# CPU-board-Sheet3-multi-rev_0_1.net
KiCad netlist of a schematic drawn in Altium Designer
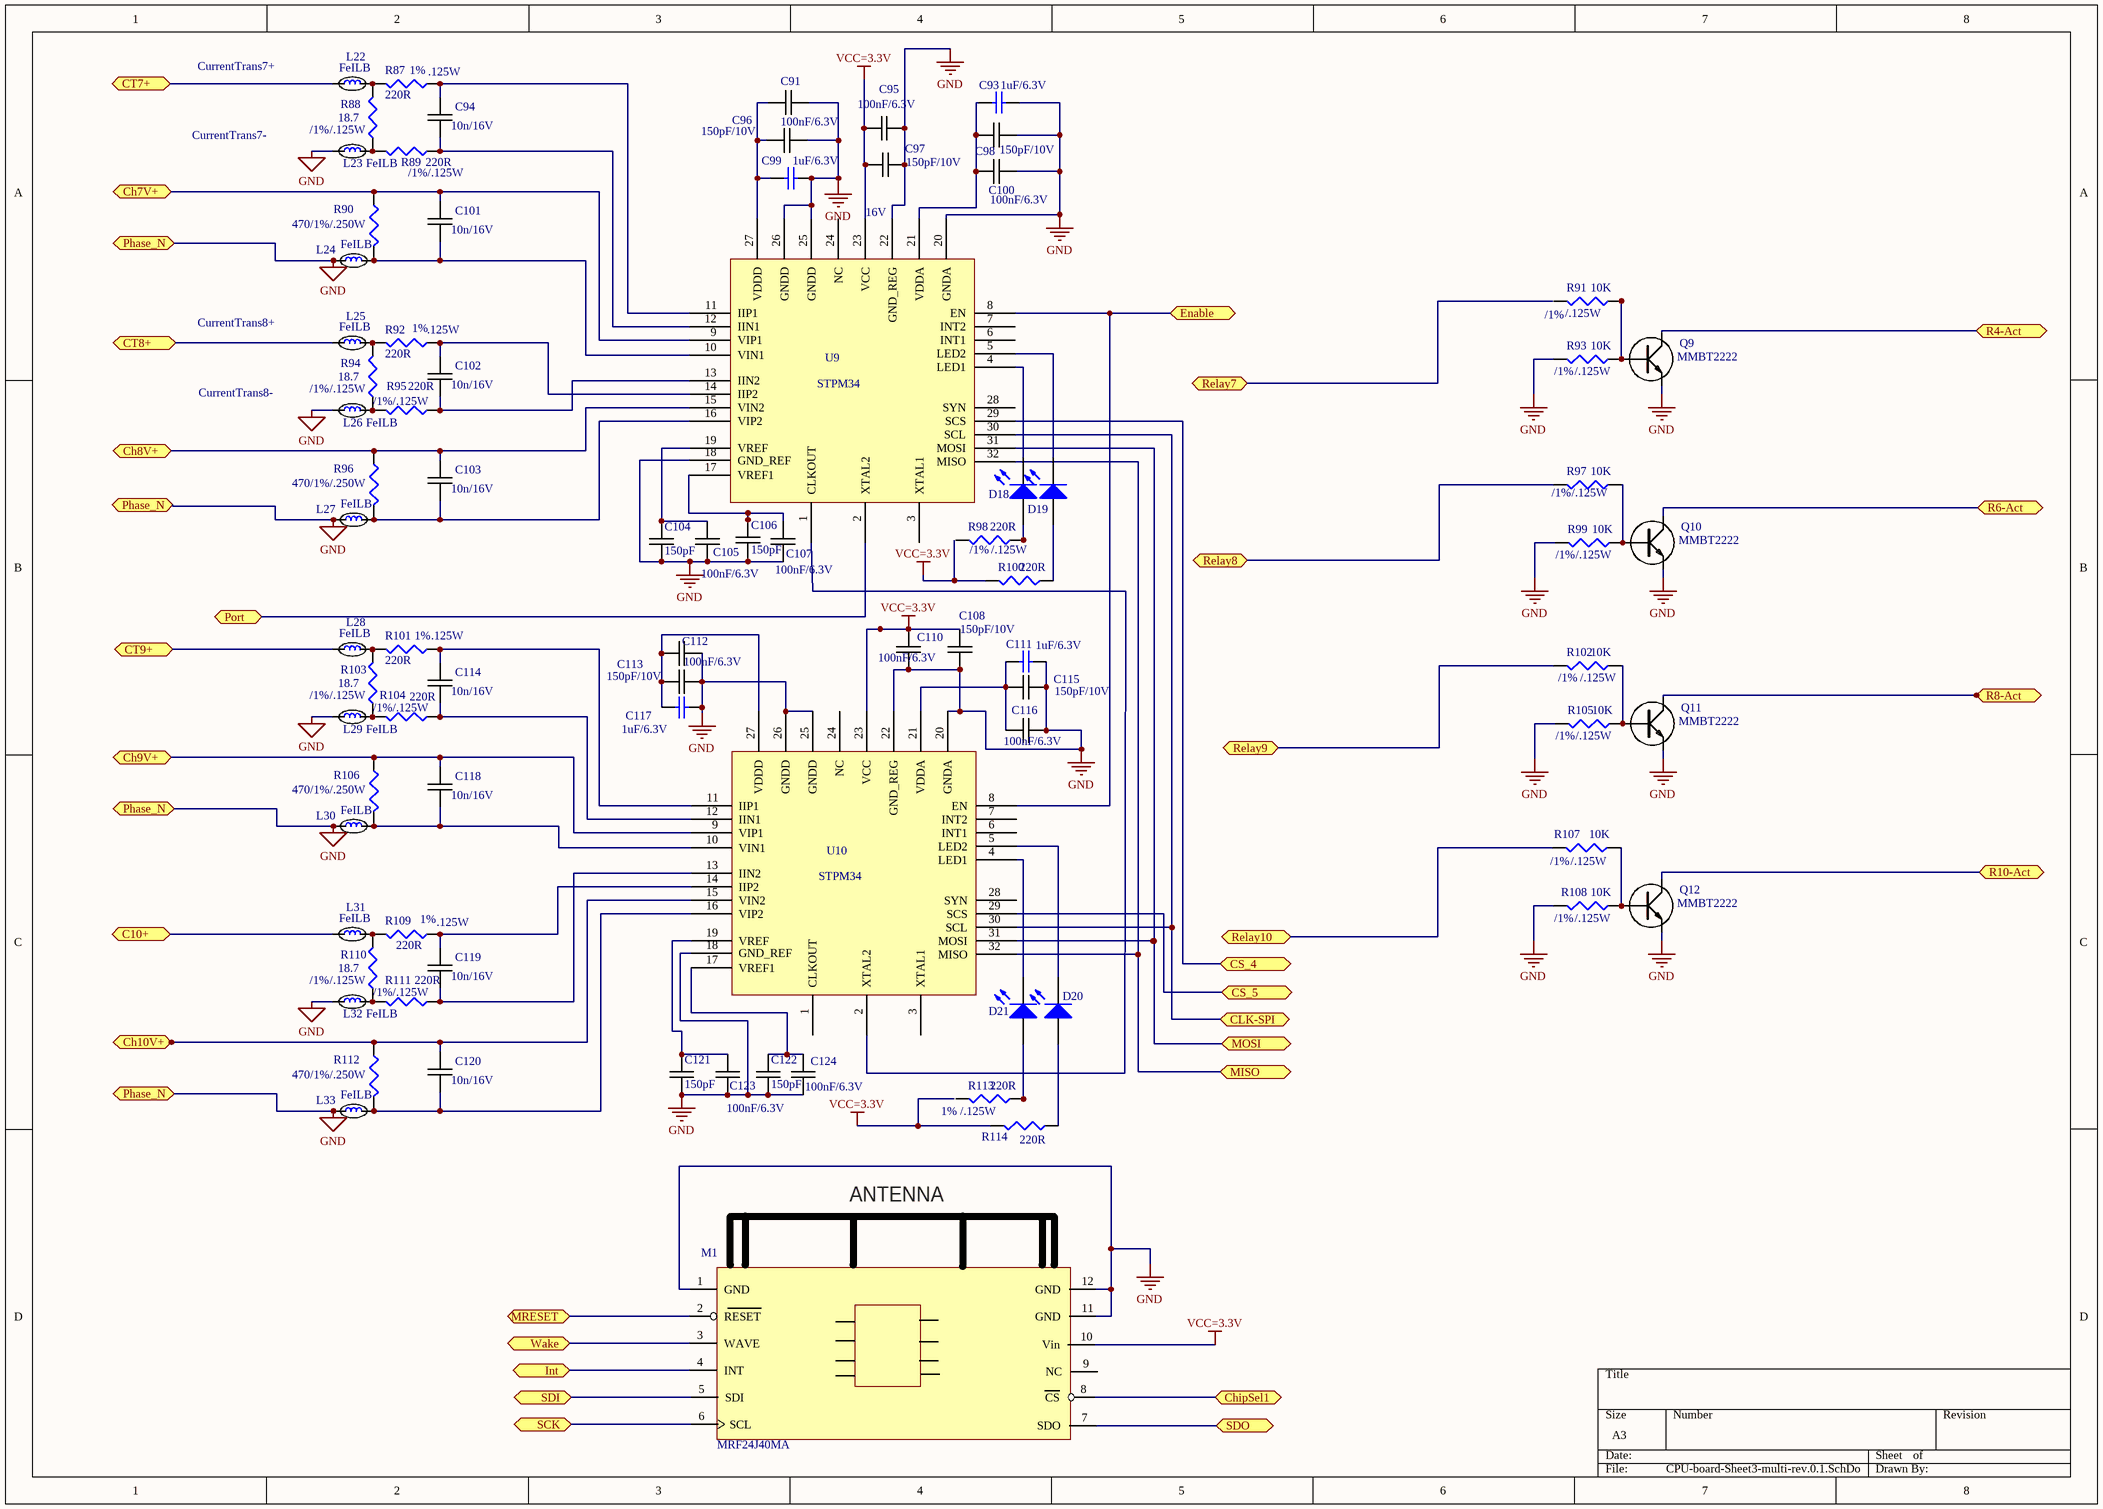
[diagram p0: CPU-board-Sheet3-multi-rev.0.1.SchDoc]

(export (version "E")
  (design (tool "Eeschema 10.0.6"))
  (components
    (comp (ref "C91")
      (value "100nF/6.3V")
      (footprint "0402C-GENERIC")
      (description "CAPACITOR 0805 CERAMIC")
      (fields (field (name "MANUFACTURER") "Taiyo Yuden"))
      (libsource (lib "vh_altium_library") (part "0805C-18PF-50V-C0G-JOH"))
    )
    (comp (ref "C93")
      (value "1uF/6.3V")
      (footprint "0402C-GENERIC")
      (description "Capacitor")
      (fields (field (name "MANUFACTURER") "Murata") (field (name "PUBLISHER") "Altium Limited"))
      (libsource (lib "Miscellaneous Devices") (part "Cap"))
    )
    (comp (ref "C94")
      (value "10n/16V")
      (footprint "0402C-GENERIC")
      (description "CAPACITOR 0805 CERAMIC")
      (fields (field (name "MANUFACTURER") "Murata Electronics"))
      (libsource (lib "vh_altium_library") (part "0805C-18PF-50V-C0G-JOH"))
    )
    (comp (ref "C95")
      (value "100nF/6.3V")
      (footprint "0402C-GENERIC")
      (description "CAPACITOR 0805 CERAMIC")
      (fields (field (name "MANUFACTURER") "Taiyo Yuden"))
      (libsource (lib "vh_altium_library") (part "0805C-18PF-50V-C0G-JOH"))
    )
    (comp (ref "C96")
      (value "150pF/10V")
      (footprint "0402C-GENERIC")
      (description "CAPACITOR 0805 CERAMIC")
      (fields (field (name "MANUFACTURER") "Wurth Electronics"))
      (libsource (lib "vh_altium_library") (part "0805C-18PF-50V-C0G-JOH"))
    )
    (comp (ref "C97")
      (value "150pF/10V")
      (footprint "0402C-GENERIC")
      (description "CAPACITOR 0805 CERAMIC")
      (fields (field (name "MANUFACTURER") "Wurth Electronics"))
      (libsource (lib "vh_altium_library") (part "0805C-18PF-50V-C0G-JOH"))
    )
    (comp (ref "C98")
      (value "150pF/10V")
      (footprint "0402C-GENERIC")
      (description "CAPACITOR 0805 CERAMIC")
      (fields (field (name "MANUFACTURER") "Wurth Electronics"))
      (libsource (lib "vh_altium_library") (part "0805C-18PF-50V-C0G-JOH"))
    )
    (comp (ref "C99")
      (value "1uF/6.3V")
      (footprint "0402C-GENERIC")
      (description "Capacitor")
      (fields (field (name "MANUFACTURER") "Murata") (field (name "PUBLISHER") "Altium Limited"))
      (libsource (lib "Miscellaneous Devices") (part "Cap"))
    )
    (comp (ref "C100")
      (value "100nF/6.3V")
      (footprint "0402C-GENERIC")
      (description "CAPACITOR 0805 CERAMIC")
      (fields (field (name "MANUFACTURER") "Taiyo Yuden"))
      (libsource (lib "vh_altium_library") (part "0805C-18PF-50V-C0G-JOH"))
    )
    (comp (ref "C101")
      (value "10n/16V")
      (footprint "0402C-GENERIC")
      (description "CAPACITOR 0805 CERAMIC")
      (fields (field (name "MANUFACTURER") "Murata Electronics"))
      (libsource (lib "vh_altium_library") (part "0805C-18PF-50V-C0G-JOH"))
    )
    (comp (ref "C102")
      (value "10n/16V")
      (footprint "0402C-GENERIC")
      (description "CAPACITOR 0805 CERAMIC")
      (fields (field (name "MANUFACTURER") "Murata Electronics"))
      (libsource (lib "vh_altium_library") (part "0805C-18PF-50V-C0G-JOH"))
    )
    (comp (ref "C103")
      (value "10n/16V")
      (footprint "0402C-GENERIC")
      (description "CAPACITOR 0805 CERAMIC")
      (fields (field (name "MANUFACTURER") "Murata Electronics"))
      (libsource (lib "vh_altium_library") (part "0805C-18PF-50V-C0G-JOH"))
    )
    (comp (ref "C104")
      (value "150pF")
      (footprint "0402C-GENERIC")
      (description "CAPACITOR 0805 CERAMIC")
      (fields (field (name "MANUFACTURER") "Wurth Electronics"))
      (libsource (lib "vh_altium_library") (part "0805C-18PF-50V-C0G-JOH"))
    )
    (comp (ref "C105")
      (value "100nF/6.3V")
      (footprint "0402C-GENERIC")
      (description "CAPACITOR 0805 CERAMIC")
      (fields (field (name "MANUFACTURER") "Taiyo Yuden"))
      (libsource (lib "vh_altium_library") (part "0805C-18PF-50V-C0G-JOH"))
    )
    (comp (ref "C106")
      (value "150pF")
      (footprint "0402C-GENERIC")
      (description "CAPACITOR 0805 CERAMIC")
      (fields (field (name "MANUFACTURER") "Wurth Electronics"))
      (libsource (lib "vh_altium_library") (part "0805C-18PF-50V-C0G-JOH"))
    )
    (comp (ref "C107")
      (value "100nF/6.3V")
      (footprint "0402C-GENERIC")
      (description "CAPACITOR 0805 CERAMIC")
      (fields (field (name "MANUFACTURER") "Taiyo Yuden"))
      (libsource (lib "vh_altium_library") (part "0805C-18PF-50V-C0G-JOH"))
    )
    (comp (ref "C108")
      (value "150pF/10V")
      (footprint "0402C-GENERIC")
      (description "CAPACITOR 0805 CERAMIC")
      (fields (field (name "MANUFACTURER") "Wurth Electronics"))
      (libsource (lib "vh_altium_library") (part "0805C-18PF-50V-C0G-JOH"))
    )
    (comp (ref "C110")
      (value "100nF/6.3V")
      (footprint "0402C-GENERIC")
      (description "CAPACITOR 0805 CERAMIC")
      (fields (field (name "MANUFACTURER") "Taiyo Yuden"))
      (libsource (lib "vh_altium_library") (part "0805C-18PF-50V-C0G-JOH"))
    )
    (comp (ref "C111")
      (value "1uF/6.3V")
      (footprint "0402C-GENERIC")
      (description "Capacitor")
      (fields (field (name "MANUFACTURER") "Murata") (field (name "PUBLISHER") "Altium Limited"))
      (libsource (lib "Miscellaneous Devices") (part "Cap"))
    )
    (comp (ref "C112")
      (value "100nF/6.3V")
      (footprint "0402C-GENERIC")
      (description "CAPACITOR 0805 CERAMIC")
      (fields (field (name "MANUFACTURER") "Taiyo Yuden"))
      (libsource (lib "vh_altium_library") (part "0805C-18PF-50V-C0G-JOH"))
    )
    (comp (ref "C113")
      (value "150pF/10V")
      (footprint "0402C-GENERIC")
      (description "CAPACITOR 0805 CERAMIC")
      (fields (field (name "MANUFACTURER") "Wurth Electronics"))
      (libsource (lib "vh_altium_library") (part "0805C-18PF-50V-C0G-JOH"))
    )
    (comp (ref "C114")
      (value "10n/16V")
      (footprint "0402C-GENERIC")
      (description "CAPACITOR 0805 CERAMIC")
      (fields (field (name "MANUFACTURER") "Murata Electronics"))
      (libsource (lib "vh_altium_library") (part "0805C-18PF-50V-C0G-JOH"))
    )
    (comp (ref "C115")
      (value "150pF/10V")
      (footprint "0402C-GENERIC")
      (description "CAPACITOR 0805 CERAMIC")
      (fields (field (name "MANUFACTURER") "Wurth Electronics"))
      (libsource (lib "vh_altium_library") (part "0805C-18PF-50V-C0G-JOH"))
    )
    (comp (ref "C116")
      (value "100nF/6.3V")
      (footprint "0402C-GENERIC")
      (description "CAPACITOR 0805 CERAMIC")
      (fields (field (name "MANUFACTURER") "Taiyo Yuden"))
      (libsource (lib "vh_altium_library") (part "0805C-18PF-50V-C0G-JOH"))
    )
    (comp (ref "C117")
      (value "1uF/6.3V")
      (footprint "0402C-GENERIC")
      (description "Capacitor")
      (fields (field (name "MANUFACTURER") "Murata") (field (name "PUBLISHER") "Altium Limited"))
      (libsource (lib "Miscellaneous Devices") (part "Cap"))
    )
    (comp (ref "C118")
      (value "10n/16V")
      (footprint "0402C-GENERIC")
      (description "CAPACITOR 0805 CERAMIC")
      (fields (field (name "MANUFACTURER") "Murata Electronics"))
      (libsource (lib "vh_altium_library") (part "0805C-18PF-50V-C0G-JOH"))
    )
    (comp (ref "C119")
      (value "10n/16V")
      (footprint "0402C-GENERIC")
      (description "CAPACITOR 0805 CERAMIC")
      (fields (field (name "MANUFACTURER") "Murata Electronics"))
      (libsource (lib "vh_altium_library") (part "0805C-18PF-50V-C0G-JOH"))
    )
    (comp (ref "C120")
      (value "10n/16V")
      (footprint "0402C-GENERIC")
      (description "CAPACITOR 0805 CERAMIC")
      (fields (field (name "MANUFACTURER") "Murata Electronics"))
      (libsource (lib "vh_altium_library") (part "0805C-18PF-50V-C0G-JOH"))
    )
    (comp (ref "C121")
      (value "150pF")
      (footprint "0402C-GENERIC")
      (description "CAPACITOR 0805 CERAMIC")
      (fields (field (name "MANUFACTURER") "Wurth Electronics"))
      (libsource (lib "vh_altium_library") (part "0805C-18PF-50V-C0G-JOH"))
    )
    (comp (ref "C122")
      (value "150pF")
      (footprint "0402C-GENERIC")
      (description "CAPACITOR 0805 CERAMIC")
      (fields (field (name "MANUFACTURER") "Wurth Electronics"))
      (libsource (lib "vh_altium_library") (part "0805C-18PF-50V-C0G-JOH"))
    )
    (comp (ref "C123")
      (value "100nF/6.3V")
      (footprint "0402C-GENERIC")
      (description "CAPACITOR 0805 CERAMIC")
      (fields (field (name "MANUFACTURER") "Taiyo Yuden"))
      (libsource (lib "vh_altium_library") (part "0805C-18PF-50V-C0G-JOH"))
    )
    (comp (ref "C124")
      (value "100nF/6.3V")
      (footprint "0402C-GENERIC")
      (description "CAPACITOR 0805 CERAMIC")
      (fields (field (name "MANUFACTURER") "Taiyo Yuden"))
      (libsource (lib "vh_altium_library") (part "0805C-18PF-50V-C0G-JOH"))
    )
    (comp (ref "D18")
      (value "LED2")
      (footprint "LED-SM")
      (description "Typical RED, GREEN, YELLOW, AMBER GaAs LED")
      (fields (field (name "MANUFACTURER") "Lite-On Inc") (field (name "PUBLISHER") "Altium Limited"))
      (libsource (lib "Miscellaneous Devices") (part "LED2"))
    )
    (comp (ref "D19")
      (value "LED2")
      (footprint "LED-SM")
      (description "Typical RED, GREEN, YELLOW, AMBER GaAs LED")
      (fields (field (name "MANUFACTURER") "Lite-On Inc") (field (name "PUBLISHER") "Altium Limited"))
      (libsource (lib "Miscellaneous Devices") (part "LED2"))
    )
    (comp (ref "D20")
      (value "LED2")
      (footprint "LED-SM")
      (description "Typical RED, GREEN, YELLOW, AMBER GaAs LED")
      (fields (field (name "MANUFACTURER") "Lite-On Inc") (field (name "PUBLISHER") "Altium Limited"))
      (libsource (lib "Miscellaneous Devices") (part "LED2"))
    )
    (comp (ref "D21")
      (value "LED2")
      (footprint "LED-SM")
      (description "Typical RED, GREEN, YELLOW, AMBER GaAs LED")
      (fields (field (name "MANUFACTURER") "Lite-On Inc") (field (name "PUBLISHER") "Altium Limited"))
      (libsource (lib "Miscellaneous Devices") (part "LED2"))
    )
    (comp (ref "L22")
      (value "FeILB")
      (footprint "0603C-TBD")
      (fields (field (name "MANUFACTURER") "Brand Samsung"))
      (libsource (lib "SMLib") (part "FerrBeads/ILBB"))
    )
    (comp (ref "L23")
      (value "FeILB")
      (footprint "0603C-TBD")
      (fields (field (name "MANUFACTURER") "Brand Samsung"))
      (libsource (lib "SMLib") (part "FerrBeads/ILBB"))
    )
    (comp (ref "L24")
      (value "FeILB")
      (footprint "0603C-TBD")
      (fields (field (name "MANUFACTURER") "Brand Samsung"))
      (libsource (lib "SMLib") (part "FerrBeads/ILBB"))
    )
    (comp (ref "L25")
      (value "FeILB")
      (footprint "0603C-TBD")
      (fields (field (name "MANUFACTURER") "Brand Samsung"))
      (libsource (lib "SMLib") (part "FerrBeads/ILBB"))
    )
    (comp (ref "L26")
      (value "FeILB")
      (footprint "0603C-TBD")
      (fields (field (name "MANUFACTURER") "Brand Samsung"))
      (libsource (lib "SMLib") (part "FerrBeads/ILBB"))
    )
    (comp (ref "L27")
      (value "FeILB")
      (footprint "0603C-TBD")
      (fields (field (name "MANUFACTURER") "Brand Samsung"))
      (libsource (lib "SMLib") (part "FerrBeads/ILBB"))
    )
    (comp (ref "L28")
      (value "FeILB")
      (footprint "0603C-TBD")
      (fields (field (name "MANUFACTURER") "Brand Samsung"))
      (libsource (lib "SMLib") (part "FerrBeads/ILBB"))
    )
    (comp (ref "L29")
      (value "FeILB")
      (footprint "0603C-TBD")
      (fields (field (name "MANUFACTURER") "Brand Samsung"))
      (libsource (lib "SMLib") (part "FerrBeads/ILBB"))
    )
    (comp (ref "L30")
      (value "FeILB")
      (footprint "0603C-TBD")
      (fields (field (name "MANUFACTURER") "Brand Samsung"))
      (libsource (lib "SMLib") (part "FerrBeads/ILBB"))
    )
    (comp (ref "L31")
      (value "FeILB")
      (footprint "0603C-TBD")
      (fields (field (name "MANUFACTURER") "Brand Samsung"))
      (libsource (lib "SMLib") (part "FerrBeads/ILBB"))
    )
    (comp (ref "L32")
      (value "FeILB")
      (footprint "0603C-TBD")
      (fields (field (name "MANUFACTURER") "Brand Samsung"))
      (libsource (lib "SMLib") (part "FerrBeads/ILBB"))
    )
    (comp (ref "L33")
      (value "FeILB")
      (footprint "0603C-TBD")
      (fields (field (name "MANUFACTURER") "Brand Samsung"))
      (libsource (lib "SMLib") (part "FerrBeads/ILBB"))
    )
    (comp (ref "M1")
      (value "MRF24J40MA")
      (footprint "MRF24J40MA-zigBEE module")
      (fields (field (name "MANUFACTURER") "Microchip"))
      (libsource (lib "SMLib") (part "MRF24J40MA"))
    )
    (comp (ref "Q9")
      (value "MMBT2222")
      (footprint "MMBT2222")
      (description "BC847 SMALL SIGNAL NPN TRANSISTOR")
      (fields (field (name "MANUFACTURER") "Diodes  Inc."))
      (libsource (lib "vh_altium_library") (part "MMBT2222"))
    )
    (comp (ref "Q10")
      (value "MMBT2222")
      (footprint "MMBT2222")
      (description "BC847 SMALL SIGNAL NPN TRANSISTOR")
      (fields (field (name "MANUFACTURER") "Diodes  Inc."))
      (libsource (lib "vh_altium_library") (part "MMBT2222"))
    )
    (comp (ref "Q11")
      (value "MMBT2222")
      (footprint "MMBT2222")
      (description "BC847 SMALL SIGNAL NPN TRANSISTOR")
      (fields (field (name "MANUFACTURER") "Diodes  Inc."))
      (libsource (lib "vh_altium_library") (part "MMBT2222"))
    )
    (comp (ref "Q12")
      (value "MMBT2222")
      (footprint "MMBT2222")
      (description "BC847 SMALL SIGNAL NPN TRANSISTOR")
      (fields (field (name "MANUFACTURER") "Diodes  Inc."))
      (libsource (lib "vh_altium_library") (part "MMBT2222"))
    )
    (comp (ref "R87")
      (value "220R")
      (footprint "0402R-TBD")
      (description "Resistor")
      (fields (field (name "MANUFACTURER") "Panasonic") (field (name "PUBLISHER") "Altium Limited"))
      (libsource (lib "Miscellaneous Devices") (part "Res3"))
    )
    (comp (ref "R88")
      (value "18.7")
      (footprint "0402R-TBD")
      (description "Resistor")
      (fields (field (name "MANUFACTURER") "Panasonic") (field (name "PUBLISHER") "Altium Limited"))
      (libsource (lib "Miscellaneous Devices") (part "Res3"))
    )
    (comp (ref "R89")
      (value "220R")
      (footprint "0402R-TBD")
      (description "Resistor")
      (fields (field (name "MANUFACTURER") "Panasonic") (field (name "PUBLISHER") "Altium Limited"))
      (libsource (lib "Miscellaneous Devices") (part "Res3"))
    )
    (comp (ref "R90")
      (value "470/1%/.250W")
      (footprint "1206FB-GENERIC")
      (description "Resistor")
      (fields (field (name "MANUFACTURER") "Panasonic Co") (field (name "PUBLISHER") "Altium Limited"))
      (libsource (lib "Miscellaneous Devices") (part "Res3"))
    )
    (comp (ref "R91")
      (value "10K")
      (footprint "0402R-TBD")
      (description "Resistor")
      (fields (field (name "MANUFACTURER") "Panasonic") (field (name "PUBLISHER") "Altium Limited"))
      (libsource (lib "Miscellaneous Devices") (part "Res3"))
    )
    (comp (ref "R92")
      (value "220R")
      (footprint "0402R-TBD")
      (description "Resistor")
      (fields (field (name "MANUFACTURER") "Panasonic") (field (name "PUBLISHER") "Altium Limited"))
      (libsource (lib "Miscellaneous Devices") (part "Res3"))
    )
    (comp (ref "R93")
      (value "10K")
      (footprint "0402R-TBD")
      (description "Resistor")
      (fields (field (name "MANUFACTURER") "Panasonic") (field (name "PUBLISHER") "Altium Limited"))
      (libsource (lib "Miscellaneous Devices") (part "Res3"))
    )
    (comp (ref "R94")
      (value "18.7")
      (footprint "0402R-TBD")
      (description "Resistor")
      (fields (field (name "MANUFACTURER") "Panasonic") (field (name "PUBLISHER") "Altium Limited"))
      (libsource (lib "Miscellaneous Devices") (part "Res3"))
    )
    (comp (ref "R95")
      (value "220R")
      (footprint "0402R-TBD")
      (description "Resistor")
      (fields (field (name "MANUFACTURER") "Panasonic") (field (name "PUBLISHER") "Altium Limited"))
      (libsource (lib "Miscellaneous Devices") (part "Res3"))
    )
    (comp (ref "R96")
      (value "470/1%/.250W")
      (footprint "1206FB-GENERIC")
      (description "Resistor")
      (fields (field (name "MANUFACTURER") "Panasonic Co") (field (name "PUBLISHER") "Altium Limited"))
      (libsource (lib "Miscellaneous Devices") (part "Res3"))
    )
    (comp (ref "R97")
      (value "10K")
      (footprint "0402R-TBD")
      (description "Resistor")
      (fields (field (name "MANUFACTURER") "Panasonic") (field (name "PUBLISHER") "Altium Limited"))
      (libsource (lib "Miscellaneous Devices") (part "Res3"))
    )
    (comp (ref "R98")
      (value "220R")
      (footprint "0402R-TBD")
      (description "Resistor")
      (fields (field (name "MANUFACTURER") "Panasonic") (field (name "PUBLISHER") "Altium Limited"))
      (libsource (lib "Miscellaneous Devices") (part "Res3"))
    )
    (comp (ref "R99")
      (value "10K")
      (footprint "0402R-TBD")
      (description "Resistor")
      (fields (field (name "MANUFACTURER") "Panasonic") (field (name "PUBLISHER") "Altium Limited"))
      (libsource (lib "Miscellaneous Devices") (part "Res3"))
    )
    (comp (ref "R100")
      (value "220R")
      (footprint "0402R-TBD")
      (description "Resistor")
      (fields (field (name "MANUFACTURER") "Panasonic") (field (name "PUBLISHER") "Altium Limited"))
      (libsource (lib "Miscellaneous Devices") (part "Res3"))
    )
    (comp (ref "R101")
      (value "220R")
      (footprint "0402R-TBD")
      (description "Resistor")
      (fields (field (name "MANUFACTURER") "Panasonic") (field (name "PUBLISHER") "Altium Limited"))
      (libsource (lib "Miscellaneous Devices") (part "Res3"))
    )
    (comp (ref "R102")
      (value "10K")
      (footprint "0402R-TBD")
      (description "Resistor")
      (fields (field (name "MANUFACTURER") "Panasonic") (field (name "PUBLISHER") "Altium Limited"))
      (libsource (lib "Miscellaneous Devices") (part "Res3"))
    )
    (comp (ref "R103")
      (value "18.7")
      (footprint "0402R-TBD")
      (description "Resistor")
      (fields (field (name "MANUFACTURER") "Panasonic") (field (name "PUBLISHER") "Altium Limited"))
      (libsource (lib "Miscellaneous Devices") (part "Res3"))
    )
    (comp (ref "R104")
      (value "220R")
      (footprint "0402R-TBD")
      (description "Resistor")
      (fields (field (name "MANUFACTURER") "Panasonic") (field (name "PUBLISHER") "Altium Limited"))
      (libsource (lib "Miscellaneous Devices") (part "Res3"))
    )
    (comp (ref "R105")
      (value "10K")
      (footprint "0402R-TBD")
      (description "Resistor")
      (fields (field (name "MANUFACTURER") "Panasonic") (field (name "PUBLISHER") "Altium Limited"))
      (libsource (lib "Miscellaneous Devices") (part "Res3"))
    )
    (comp (ref "R106")
      (value "470/1%/.250W")
      (footprint "1206FB-GENERIC")
      (description "Resistor")
      (fields (field (name "MANUFACTURER") "Panasonic Co") (field (name "PUBLISHER") "Altium Limited"))
      (libsource (lib "Miscellaneous Devices") (part "Res3"))
    )
    (comp (ref "R107")
      (value "10K")
      (footprint "0402R-TBD")
      (description "Resistor")
      (fields (field (name "MANUFACTURER") "Panasonic") (field (name "PUBLISHER") "Altium Limited"))
      (libsource (lib "Miscellaneous Devices") (part "Res3"))
    )
    (comp (ref "R108")
      (value "10K")
      (footprint "0402R-TBD")
      (description "Resistor")
      (fields (field (name "MANUFACTURER") "Panasonic") (field (name "PUBLISHER") "Altium Limited"))
      (libsource (lib "Miscellaneous Devices") (part "Res3"))
    )
    (comp (ref "R109")
      (value "220R")
      (footprint "0402R-TBD")
      (description "Resistor")
      (fields (field (name "MANUFACTURER") "Panasonic") (field (name "PUBLISHER") "Altium Limited"))
      (libsource (lib "Miscellaneous Devices") (part "Res3"))
    )
    (comp (ref "R110")
      (value "18.7")
      (footprint "0402R-TBD")
      (description "Resistor")
      (fields (field (name "MANUFACTURER") "Panasonic") (field (name "PUBLISHER") "Altium Limited"))
      (libsource (lib "Miscellaneous Devices") (part "Res3"))
    )
    (comp (ref "R111")
      (value "220R")
      (footprint "0402R-TBD")
      (description "Resistor")
      (fields (field (name "MANUFACTURER") "Panasonic") (field (name "PUBLISHER") "Altium Limited"))
      (libsource (lib "Miscellaneous Devices") (part "Res3"))
    )
    (comp (ref "R112")
      (value "470/1%/.250W")
      (footprint "1206FB-GENERIC")
      (description "Resistor")
      (fields (field (name "MANUFACTURER") "Panasonic Co") (field (name "PUBLISHER") "Altium Limited"))
      (libsource (lib "Miscellaneous Devices") (part "Res3"))
    )
    (comp (ref "R113")
      (value "220R")
      (footprint "0402R-TBD")
      (description "Resistor")
      (fields (field (name "MANUFACTURER") "Panasonic") (field (name "PUBLISHER") "Altium Limited"))
      (libsource (lib "Miscellaneous Devices") (part "Res3"))
    )
    (comp (ref "R114")
      (value "220R")
      (footprint "0402R-TBD")
      (description "Resistor")
      (fields (field (name "MANUFACTURER") "Panasonic") (field (name "PUBLISHER") "Altium Limited"))
      (libsource (lib "Miscellaneous Devices") (part "Res3"))
    )
    (comp (ref "U9")
      (value "STPM34")
      (footprint "Atmel Microcontroller 8-Bit megaAVR:QFN32_L")
      (libsource (lib "SMLib") (part "STPM34"))
    )
    (comp (ref "U10")
      (value "STPM34")
      (footprint "Atmel Microcontroller 8-Bit megaAVR:QFN32_L")
      (libsource (lib "SMLib") (part "STPM34"))
    )
  )
  (nets
    (net (code "1") (name "/C10+") (class "Default")
      (node (ref "L31") (pin "1") (pinfunction "1_1") (pintype "passive"))
    )
    (net (code "2") (name "/CLK-SPI") (class "Default")
      (node (ref "U10") (pin "30") (pinfunction "SCL_30") (pintype "passive"))
      (node (ref "U9") (pin "30") (pinfunction "SCL_30") (pintype "passive"))
    )
    (net (code "3") (name "/CS_4") (class "Default")
      (node (ref "U9") (pin "29") (pinfunction "SCS_29") (pintype "passive"))
    )
    (net (code "4") (name "/CS_5") (class "Default")
      (node (ref "U10") (pin "29") (pinfunction "SCS_29") (pintype "passive"))
    )
    (net (code "5") (name "/CT7+") (class "Default")
      (node (ref "L22") (pin "1") (pinfunction "1_1") (pintype "passive"))
    )
    (net (code "6") (name "/CT8+") (class "Default")
      (node (ref "L25") (pin "1") (pinfunction "1_1") (pintype "passive"))
    )
    (net (code "7") (name "/CT9+") (class "Default")
      (node (ref "L28") (pin "1") (pinfunction "1_1") (pintype "passive"))
    )
    (net (code "8") (name "/Ch7V+") (class "Default")
      (node (ref "C101") (pin "2") (pintype "passive"))
      (node (ref "R90") (pin "1") (pinfunction "1_1") (pintype "passive"))
      (node (ref "U9") (pin "9") (pinfunction "VIP1_9") (pintype "passive"))
    )
    (net (code "9") (name "/Ch8V+") (class "Default")
      (node (ref "C103") (pin "2") (pintype "passive"))
      (node (ref "R96") (pin "1") (pinfunction "1_1") (pintype "passive"))
      (node (ref "U9") (pin "15") (pinfunction "VIN2_15") (pintype "passive"))
    )
    (net (code "10") (name "/Ch9V+") (class "Default")
      (node (ref "C118") (pin "2") (pintype "passive"))
      (node (ref "R106") (pin "1") (pinfunction "1_1") (pintype "passive"))
      (node (ref "U10") (pin "9") (pinfunction "VIP1_9") (pintype "passive"))
    )
    (net (code "11") (name "/Ch10V+") (class "Default")
      (node (ref "C120") (pin "2") (pintype "passive"))
      (node (ref "R112") (pin "1") (pinfunction "1_1") (pintype "passive"))
      (node (ref "U10") (pin "15") (pinfunction "VIN2_15") (pintype "passive"))
    )
    (net (code "12") (name "/ChipSel1") (class "Default")
      (node (ref "M1") (pin "8") (pinfunction "CS_8") (pintype "passive"))
    )
    (net (code "13") (name "/Enable") (class "Default")
      (node (ref "U10") (pin "8") (pinfunction "EN_8") (pintype "passive"))
      (node (ref "U9") (pin "8") (pinfunction "EN_8") (pintype "passive"))
    )
    (net (code "14") (name "/Int") (class "Default")
      (node (ref "M1") (pin "4") (pinfunction "INT_4") (pintype "passive"))
    )
    (net (code "15") (name "/MISO") (class "Default")
      (node (ref "U10") (pin "32") (pinfunction "MISO_32") (pintype "passive"))
      (node (ref "U9") (pin "32") (pinfunction "MISO_32") (pintype "passive"))
    )
    (net (code "16") (name "/MOSI") (class "Default")
      (node (ref "U10") (pin "31") (pinfunction "MOSI_31") (pintype "passive"))
      (node (ref "U9") (pin "31") (pinfunction "MOSI_31") (pintype "passive"))
    )
    (net (code "17") (name "/MRESET") (class "Default")
      (node (ref "M1") (pin "2") (pinfunction "RESET_2") (pintype "passive"))
    )
    (net (code "18") (name "/Port") (class "Default")
      (node (ref "U9") (pin "2") (pinfunction "XTAL2_2") (pintype "passive"))
    )
    (net (code "19") (name "/R4-Act") (class "Default") (node (ref "Q9") (pin "C") (pintype "passive")))
    (net (code "20") (name "/R6-Act") (class "Default") (node (ref "Q10") (pin "C") (pintype "passive")))
    (net (code "21") (name "/R8-Act") (class "Default") (node (ref "Q11") (pin "C") (pintype "passive")))
    (net (code "22") (name "/R10-Act") (class "Default") (node (ref "Q12") (pin "C") (pintype "passive")))
    (net (code "24") (name "/Relay8") (class "Default")
      (node (ref "R97") (pin "2") (pinfunction "2_2") (pintype "passive"))
    )
    (net (code "25") (name "/Relay9") (class "Default")
      (node (ref "R102") (pin "2") (pinfunction "2_2") (pintype "passive"))
    )
    (net (code "26") (name "/Relay10") (class "Default")
      (node (ref "R107") (pin "2") (pinfunction "2_2") (pintype "passive"))
    )
    (net (code "27") (name "/SCK") (class "Default")
      (node (ref "M1") (pin "6") (pinfunction "SCL_6") (pintype "passive"))
    )
    (net (code "28") (name "/SDI") (class "Default")
      (node (ref "M1") (pin "5") (pinfunction "SDI_5") (pintype "passive"))
    )
    (net (code "29") (name "/SDO") (class "Default")
      (node (ref "M1") (pin "7") (pinfunction "SDO_7") (pintype "passive"))
    )
    (net (code "30") (name "/Wake") (class "Default")
      (node (ref "M1") (pin "3") (pinfunction "WAVE_3") (pintype "passive"))
    )
    (net (code "31") (name "GND") (class "Default")
      (node (ref "C100") (pin "2") (pintype "passive"))
      (node (ref "C104") (pin "2") (pintype "passive"))
      (node (ref "C105") (pin "2") (pintype "passive"))
      (node (ref "C106") (pin "2") (pintype "passive"))
      (node (ref "C107") (pin "2") (pintype "passive"))
      (node (ref "C108") (pin "2") (pintype "passive"))
      (node (ref "C110") (pin "1") (pintype "passive"))
      (node (ref "C111") (pin "2") (pinfunction "2_2") (pintype "passive"))
      (node (ref "C112") (pin "2") (pintype "passive"))
      (node (ref "C113") (pin "2") (pintype "passive"))
      (node (ref "C115") (pin "2") (pintype "passive"))
      (node (ref "C116") (pin "2") (pintype "passive"))
      (node (ref "C117") (pin "2") (pinfunction "2_2") (pintype "passive"))
      (node (ref "C121") (pin "2") (pintype "passive"))
      (node (ref "C122") (pin "2") (pintype "passive"))
      (node (ref "C123") (pin "2") (pintype "passive"))
      (node (ref "C124") (pin "2") (pintype "passive"))
      (node (ref "C91") (pin "2") (pintype "passive"))
      (node (ref "C93") (pin "2") (pinfunction "2_2") (pintype "passive"))
      (node (ref "C95") (pin "2") (pintype "passive"))
      (node (ref "C96") (pin "2") (pintype "passive"))
      (node (ref "C97") (pin "2") (pintype "passive"))
      (node (ref "C98") (pin "1") (pintype "passive"))
      (node (ref "C99") (pin "2") (pinfunction "2_2") (pintype "passive"))
      (node (ref "L23") (pin "1") (pinfunction "1_1") (pintype "passive"))
      (node (ref "L24") (pin "1") (pinfunction "1_1") (pintype "passive"))
      (node (ref "L26") (pin "1") (pinfunction "1_1") (pintype "passive"))
      (node (ref "L27") (pin "1") (pinfunction "1_1") (pintype "passive"))
      (node (ref "L29") (pin "1") (pinfunction "1_1") (pintype "passive"))
      (node (ref "L30") (pin "1") (pinfunction "1_1") (pintype "passive"))
      (node (ref "L32") (pin "1") (pinfunction "1_1") (pintype "passive"))
      (node (ref "L33") (pin "1") (pinfunction "1_1") (pintype "passive"))
      (node (ref "M1") (pin "1") (pinfunction "GND_1") (pintype "passive"))
      (node (ref "M1") (pin "11") (pinfunction "GND_11") (pintype "passive"))
      (node (ref "M1") (pin "12") (pinfunction "GND_12") (pintype "passive"))
      (node (ref "Q10") (pin "E") (pintype "passive"))
      (node (ref "Q11") (pin "E") (pintype "passive"))
      (node (ref "Q12") (pin "E") (pintype "passive"))
      (node (ref "Q9") (pin "E") (pintype "passive"))
      (node (ref "R105") (pin "2") (pinfunction "2_2") (pintype "passive"))
      (node (ref "R108") (pin "2") (pinfunction "2_2") (pintype "passive"))
      (node (ref "R93") (pin "2") (pinfunction "2_2") (pintype "passive"))
      (node (ref "R99") (pin "2") (pinfunction "2_2") (pintype "passive"))
      (node (ref "U10") (pin "18") (pinfunction "GND_REF_18") (pintype "passive"))
      (node (ref "U10") (pin "20") (pinfunction "GNDA_20") (pintype "passive"))
      (node (ref "U10") (pin "22") (pinfunction "GND_REG_22") (pintype "passive"))
      (node (ref "U10") (pin "25") (pinfunction "GNDD_25") (pintype "passive"))
      (node (ref "U10") (pin "26") (pinfunction "GNDD_26") (pintype "passive"))
      (node (ref "U9") (pin "18") (pinfunction "GND_REF_18") (pintype "passive"))
      (node (ref "U9") (pin "20") (pinfunction "GNDA_20") (pintype "passive"))
      (node (ref "U9") (pin "22") (pinfunction "GND_REG_22") (pintype "passive"))
      (node (ref "U9") (pin "25") (pinfunction "GNDD_25") (pintype "passive"))
      (node (ref "U9") (pin "26") (pinfunction "GNDD_26") (pintype "passive"))
    )
    (net (code "32") (name "Net-(D18-A)") (class "Default")
      (node (ref "D18") (pin "1") (pinfunction "A_1") (pintype "passive"))
      (node (ref "R98") (pin "1") (pinfunction "1_1") (pintype "passive"))
    )
    (net (code "33") (name "Net-(D18-K)") (class "Default")
      (node (ref "D18") (pin "2") (pinfunction "K_2") (pintype "passive"))
      (node (ref "U9") (pin "4") (pinfunction "LED1_4") (pintype "passive"))
    )
    (net (code "34") (name "Net-(D19-A)") (class "Default")
      (node (ref "D19") (pin "1") (pinfunction "A_1") (pintype "passive"))
      (node (ref "R100") (pin "1") (pinfunction "1_1") (pintype "passive"))
    )
    (net (code "35") (name "Net-(D19-K)") (class "Default")
      (node (ref "D19") (pin "2") (pinfunction "K_2") (pintype "passive"))
      (node (ref "U9") (pin "5") (pinfunction "LED2_5") (pintype "passive"))
    )
    (net (code "36") (name "Net-(D20-A)") (class "Default")
      (node (ref "D20") (pin "1") (pinfunction "A_1") (pintype "passive"))
      (node (ref "R114") (pin "1") (pinfunction "1_1") (pintype "passive"))
    )
    (net (code "37") (name "Net-(D20-K)") (class "Default")
      (node (ref "D20") (pin "2") (pinfunction "K_2") (pintype "passive"))
      (node (ref "U10") (pin "5") (pinfunction "LED2_5") (pintype "passive"))
    )
    (net (code "38") (name "Net-(D21-A)") (class "Default")
      (node (ref "D21") (pin "1") (pinfunction "A_1") (pintype "passive"))
      (node (ref "R113") (pin "1") (pinfunction "1_1") (pintype "passive"))
    )
    (net (code "39") (name "Net-(D21-K)") (class "Default")
      (node (ref "D21") (pin "2") (pinfunction "K_2") (pintype "passive"))
      (node (ref "U10") (pin "4") (pinfunction "LED1_4") (pintype "passive"))
    )
    (net (code "40") (name "Net-(L22-Pad2)") (class "Default")
      (node (ref "L22") (pin "2") (pinfunction "2_2") (pintype "passive"))
      (node (ref "R87") (pin "2") (pinfunction "2_2") (pintype "passive"))
      (node (ref "R88") (pin "2") (pinfunction "2_2") (pintype "passive"))
    )
    (net (code "41") (name "Net-(L23-Pad2)") (class "Default")
      (node (ref "L23") (pin "2") (pinfunction "2_2") (pintype "passive"))
      (node (ref "R88") (pin "1") (pinfunction "1_1") (pintype "passive"))
      (node (ref "R89") (pin "2") (pinfunction "2_2") (pintype "passive"))
    )
    (net (code "42") (name "Net-(L25-Pad2)") (class "Default")
      (node (ref "L25") (pin "2") (pinfunction "2_2") (pintype "passive"))
      (node (ref "R92") (pin "2") (pinfunction "2_2") (pintype "passive"))
      (node (ref "R94") (pin "2") (pinfunction "2_2") (pintype "passive"))
    )
    (net (code "43") (name "Net-(L26-Pad2)") (class "Default")
      (node (ref "L26") (pin "2") (pinfunction "2_2") (pintype "passive"))
      (node (ref "R94") (pin "1") (pinfunction "1_1") (pintype "passive"))
      (node (ref "R95") (pin "2") (pinfunction "2_2") (pintype "passive"))
    )
    (net (code "44") (name "Net-(L28-Pad2)") (class "Default")
      (node (ref "L28") (pin "2") (pinfunction "2_2") (pintype "passive"))
      (node (ref "R101") (pin "2") (pinfunction "2_2") (pintype "passive"))
      (node (ref "R103") (pin "2") (pinfunction "2_2") (pintype "passive"))
    )
    (net (code "45") (name "Net-(L29-Pad2)") (class "Default")
      (node (ref "L29") (pin "2") (pinfunction "2_2") (pintype "passive"))
      (node (ref "R103") (pin "1") (pinfunction "1_1") (pintype "passive"))
      (node (ref "R104") (pin "2") (pinfunction "2_2") (pintype "passive"))
    )
    (net (code "46") (name "Net-(L31-Pad2)") (class "Default")
      (node (ref "L31") (pin "2") (pinfunction "2_2") (pintype "passive"))
      (node (ref "R109") (pin "2") (pinfunction "2_2") (pintype "passive"))
      (node (ref "R110") (pin "2") (pinfunction "2_2") (pintype "passive"))
    )
    (net (code "47") (name "Net-(L32-Pad2)") (class "Default")
      (node (ref "L32") (pin "2") (pinfunction "2_2") (pintype "passive"))
      (node (ref "R110") (pin "1") (pinfunction "1_1") (pintype "passive"))
      (node (ref "R111") (pin "2") (pinfunction "2_2") (pintype "passive"))
    )
    (net (code "48") (name "Net-(Q9-PadB)") (class "Default")
      (node (ref "Q9") (pin "B") (pintype "passive"))
      (node (ref "R91") (pin "1") (pinfunction "1_1") (pintype "passive"))
      (node (ref "R93") (pin "1") (pinfunction "1_1") (pintype "passive"))
    )
    (net (code "49") (name "Net-(Q10-PadB)") (class "Default")
      (node (ref "Q10") (pin "B") (pintype "passive"))
      (node (ref "R97") (pin "1") (pinfunction "1_1") (pintype "passive"))
      (node (ref "R99") (pin "1") (pinfunction "1_1") (pintype "passive"))
    )
    (net (code "50") (name "Net-(Q11-PadB)") (class "Default")
      (node (ref "Q11") (pin "B") (pintype "passive"))
      (node (ref "R102") (pin "1") (pinfunction "1_1") (pintype "passive"))
      (node (ref "R105") (pin "1") (pinfunction "1_1") (pintype "passive"))
    )
    (net (code "51") (name "Net-(Q12-PadB)") (class "Default")
      (node (ref "Q12") (pin "B") (pintype "passive"))
      (node (ref "R107") (pin "1") (pinfunction "1_1") (pintype "passive"))
      (node (ref "R108") (pin "1") (pinfunction "1_1") (pintype "passive"))
    )
    (net (code "52") (name "Net-(U9-IIN1)") (class "Default")
      (node (ref "C94") (pin "1") (pintype "passive"))
      (node (ref "R89") (pin "1") (pinfunction "1_1") (pintype "passive"))
      (node (ref "U9") (pin "12") (pinfunction "IIN1_12") (pintype "passive"))
    )
    (net (code "53") (name "Net-(U9-IIN2)") (class "Default")
      (node (ref "C102") (pin "1") (pintype "passive"))
      (node (ref "R95") (pin "1") (pinfunction "1_1") (pintype "passive"))
      (node (ref "U9") (pin "13") (pinfunction "IIN2_13") (pintype "passive"))
    )
    (net (code "54") (name "Net-(U9-IIP1)") (class "Default")
      (node (ref "C94") (pin "2") (pintype "passive"))
      (node (ref "R87") (pin "1") (pinfunction "1_1") (pintype "passive"))
      (node (ref "U9") (pin "11") (pinfunction "IIP1_11") (pintype "passive"))
    )
    (net (code "55") (name "Net-(U9-IIP2)") (class "Default")
      (node (ref "C102") (pin "2") (pintype "passive"))
      (node (ref "R92") (pin "1") (pinfunction "1_1") (pintype "passive"))
      (node (ref "U9") (pin "14") (pinfunction "IIP2_14") (pintype "passive"))
    )
    (net (code "56") (name "Net-(U9-VDDA)") (class "Default")
      (node (ref "C100") (pin "1") (pintype "passive"))
      (node (ref "C93") (pin "1") (pinfunction "1_1") (pintype "passive"))
      (node (ref "C98") (pin "2") (pintype "passive"))
      (node (ref "U9") (pin "21") (pinfunction "VDDA_21") (pintype "passive"))
    )
    (net (code "57") (name "Net-(U9-VDDD)") (class "Default")
      (node (ref "C91") (pin "1") (pintype "passive"))
      (node (ref "C96") (pin "1") (pintype "passive"))
      (node (ref "C99") (pin "1") (pinfunction "1_1") (pintype "passive"))
      (node (ref "U9") (pin "27") (pinfunction "VDDD_27") (pintype "passive"))
    )
    (net (code "58") (name "Net-(U9-VIN1)") (class "Default")
      (node (ref "C101") (pin "1") (pintype "passive"))
      (node (ref "L24") (pin "2") (pinfunction "2_2") (pintype "passive"))
      (node (ref "R90") (pin "2") (pinfunction "2_2") (pintype "passive"))
      (node (ref "U9") (pin "10") (pinfunction "VIN1_10") (pintype "passive"))
    )
    (net (code "59") (name "Net-(U9-VIP2)") (class "Default")
      (node (ref "C103") (pin "1") (pintype "passive"))
      (node (ref "L27") (pin "2") (pinfunction "2_2") (pintype "passive"))
      (node (ref "R96") (pin "2") (pinfunction "2_2") (pintype "passive"))
      (node (ref "U9") (pin "16") (pinfunction "VIP2_16") (pintype "passive"))
    )
    (net (code "60") (name "Net-(U9-VREF)") (class "Default")
      (node (ref "C104") (pin "1") (pintype "passive"))
      (node (ref "C105") (pin "1") (pintype "passive"))
      (node (ref "U9") (pin "19") (pinfunction "VREF_19") (pintype "passive"))
    )
    (net (code "61") (name "Net-(U9-VREF1)") (class "Default")
      (node (ref "C106") (pin "1") (pintype "passive"))
      (node (ref "C107") (pin "1") (pintype "passive"))
      (node (ref "U9") (pin "17") (pinfunction "VREF1_17") (pintype "passive"))
    )
    (net (code "62") (name "Net-(U10-IIN1)") (class "Default")
      (node (ref "C114") (pin "1") (pintype "passive"))
      (node (ref "R104") (pin "1") (pinfunction "1_1") (pintype "passive"))
      (node (ref "U10") (pin "12") (pinfunction "IIN1_12") (pintype "passive"))
    )
    (net (code "63") (name "Net-(U10-IIN2)") (class "Default")
      (node (ref "C119") (pin "1") (pintype "passive"))
      (node (ref "R111") (pin "1") (pinfunction "1_1") (pintype "passive"))
      (node (ref "U10") (pin "13") (pinfunction "IIN2_13") (pintype "passive"))
    )
    (net (code "64") (name "Net-(U10-IIP1)") (class "Default")
      (node (ref "C114") (pin "2") (pintype "passive"))
      (node (ref "R101") (pin "1") (pinfunction "1_1") (pintype "passive"))
      (node (ref "U10") (pin "11") (pinfunction "IIP1_11") (pintype "passive"))
    )
    (net (code "65") (name "Net-(U10-IIP2)") (class "Default")
      (node (ref "C119") (pin "2") (pintype "passive"))
      (node (ref "R109") (pin "1") (pinfunction "1_1") (pintype "passive"))
      (node (ref "U10") (pin "14") (pinfunction "IIP2_14") (pintype "passive"))
    )
    (net (code "66") (name "Net-(U10-VDDA)") (class "Default")
      (node (ref "C111") (pin "1") (pinfunction "1_1") (pintype "passive"))
      (node (ref "C115") (pin "1") (pintype "passive"))
      (node (ref "C116") (pin "1") (pintype "passive"))
      (node (ref "U10") (pin "21") (pinfunction "VDDA_21") (pintype "passive"))
    )
    (net (code "67") (name "Net-(U10-VDDD)") (class "Default")
      (node (ref "C112") (pin "1") (pintype "passive"))
      (node (ref "C113") (pin "1") (pintype "passive"))
      (node (ref "C117") (pin "1") (pinfunction "1_1") (pintype "passive"))
      (node (ref "U10") (pin "27") (pinfunction "VDDD_27") (pintype "passive"))
    )
    (net (code "68") (name "Net-(U10-VIN1)") (class "Default")
      (node (ref "C118") (pin "1") (pintype "passive"))
      (node (ref "L30") (pin "2") (pinfunction "2_2") (pintype "passive"))
      (node (ref "R106") (pin "2") (pinfunction "2_2") (pintype "passive"))
      (node (ref "U10") (pin "10") (pinfunction "VIN1_10") (pintype "passive"))
    )
    (net (code "69") (name "Net-(U10-VIP2)") (class "Default")
      (node (ref "C120") (pin "1") (pintype "passive"))
      (node (ref "L33") (pin "2") (pinfunction "2_2") (pintype "passive"))
      (node (ref "R112") (pin "2") (pinfunction "2_2") (pintype "passive"))
      (node (ref "U10") (pin "16") (pinfunction "VIP2_16") (pintype "passive"))
    )
    (net (code "70") (name "Net-(U10-VREF)") (class "Default")
      (node (ref "C121") (pin "1") (pintype "passive"))
      (node (ref "C123") (pin "1") (pintype "passive"))
      (node (ref "U10") (pin "19") (pinfunction "VREF_19") (pintype "passive"))
    )
    (net (code "71") (name "Net-(U10-VREF1)") (class "Default")
      (node (ref "C122") (pin "1") (pintype "passive"))
      (node (ref "C124") (pin "1") (pintype "passive"))
      (node (ref "U10") (pin "17") (pinfunction "VREF1_17") (pintype "passive"))
    )
    (net (code "72") (name "Net-(U10-XTAL2)") (class "Default")
      (node (ref "U10") (pin "2") (pinfunction "XTAL2_2") (pintype "passive"))
      (node (ref "U9") (pin "1") (pinfunction "CLKOUT_1") (pintype "passive"))
    )
    (net (code "73") (name "VCC=3.3V") (class "Default")
      (node (ref "C108") (pin "1") (pintype "passive"))
      (node (ref "C110") (pin "2") (pintype "passive"))
      (node (ref "C95") (pin "1") (pintype "passive"))
      (node (ref "C97") (pin "1") (pintype "passive"))
      (node (ref "M1") (pin "10") (pinfunction "Vin_10") (pintype "passive"))
      (node (ref "R100") (pin "2") (pinfunction "2_2") (pintype "passive"))
      (node (ref "R114") (pin "2") (pinfunction "2_2") (pintype "passive"))
      (node (ref "U10") (pin "23") (pinfunction "VCC_23") (pintype "passive"))
      (node (ref "U9") (pin "23") (pinfunction "VCC_23") (pintype "passive"))
    )
    (net (code "74") (name "unconnected-(M1-NC-Pad9)") (class "Default")
      (node (ref "M1") (pin "9") (pinfunction "NC_9") (pintype "passive"))
    )
    (net (code "75") (name "unconnected-(R91-Pad2)") (class "Default")
      (node (ref "R91") (pin "2") (pinfunction "2_2") (pintype "passive"))
    )
    (net (code "76") (name "unconnected-(R98-Pad2)") (class "Default")
      (node (ref "R98") (pin "2") (pinfunction "2_2") (pintype "passive"))
    )
    (net (code "77") (name "unconnected-(R113-Pad2)") (class "Default")
      (node (ref "R113") (pin "2") (pinfunction "2_2") (pintype "passive"))
    )
    (net (code "78") (name "unconnected-(U9-INT1-Pad6)") (class "Default")
      (node (ref "U9") (pin "6") (pinfunction "INT1_6") (pintype "passive"))
    )
    (net (code "79") (name "unconnected-(U9-INT2-Pad7)") (class "Default")
      (node (ref "U9") (pin "7") (pinfunction "INT2_7") (pintype "passive"))
    )
    (net (code "80") (name "unconnected-(U9-NC-Pad24)") (class "Default")
      (node (ref "U9") (pin "24") (pinfunction "NC_24") (pintype "passive"))
    )
    (net (code "81") (name "unconnected-(U9-SYN-Pad28)") (class "Default")
      (node (ref "U9") (pin "28") (pinfunction "SYN_28") (pintype "passive"))
    )
    (net (code "82") (name "unconnected-(U9-XTAL1-Pad3)") (class "Default")
      (node (ref "U9") (pin "3") (pinfunction "XTAL1_3") (pintype "passive"))
    )
    (net (code "83") (name "unconnected-(U10-CLKOUT-Pad1)") (class "Default")
      (node (ref "U10") (pin "1") (pinfunction "CLKOUT_1") (pintype "passive"))
    )
    (net (code "84") (name "unconnected-(U10-INT1-Pad6)") (class "Default")
      (node (ref "U10") (pin "6") (pinfunction "INT1_6") (pintype "passive"))
    )
    (net (code "85") (name "unconnected-(U10-INT2-Pad7)") (class "Default")
      (node (ref "U10") (pin "7") (pinfunction "INT2_7") (pintype "passive"))
    )
    (net (code "86") (name "unconnected-(U10-NC-Pad24)") (class "Default")
      (node (ref "U10") (pin "24") (pinfunction "NC_24") (pintype "passive"))
    )
    (net (code "87") (name "unconnected-(U10-SYN-Pad28)") (class "Default")
      (node (ref "U10") (pin "28") (pinfunction "SYN_28") (pintype "passive"))
    )
    (net (code "88") (name "unconnected-(U10-XTAL1-Pad3)") (class "Default")
      (node (ref "U10") (pin "3") (pinfunction "XTAL1_3") (pintype "passive"))
    )
  )
)
